# audio.net
KiCad netlist of a schematic drawn in Altium Designer
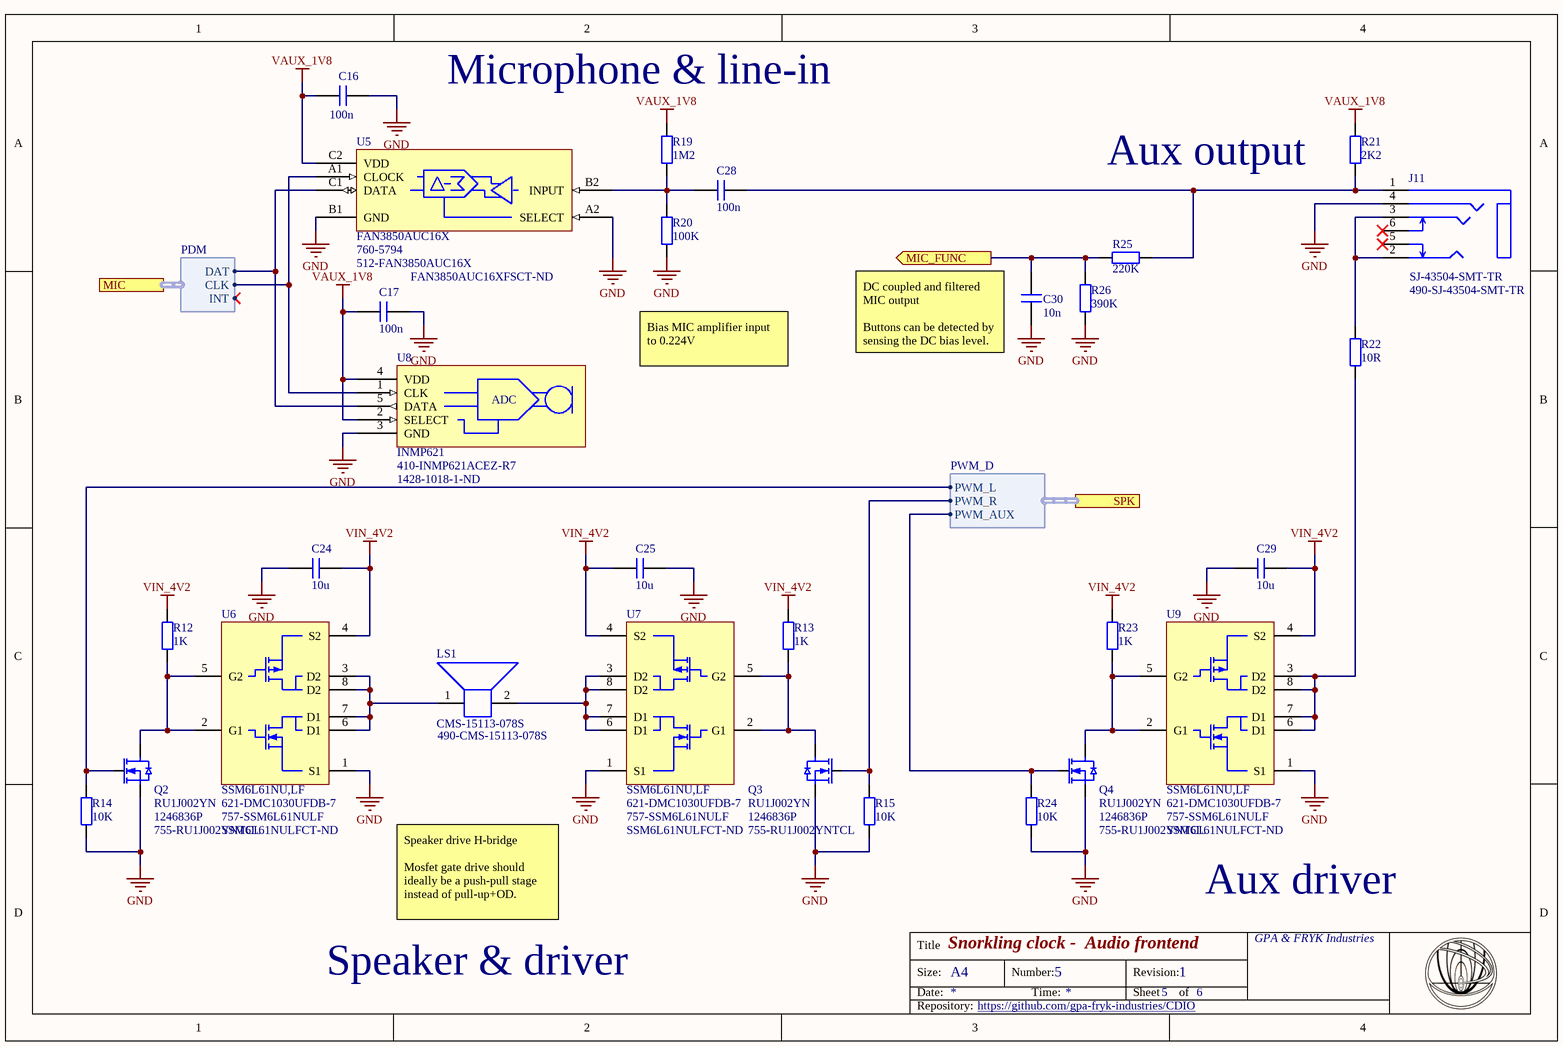
[diagram p0: audio.SchDoc]

(export (version "E")
  (design (tool "Eeschema 10.0.6"))
  (components
    (comp (ref "C16")
      (value "100n")
      (footprint "CAPC1005X06N")
      (description "Capacitor")
      (fields (field (name "Comment") "cap"))
      (libsource (lib "lib_passives") (part "cap"))
    )
    (comp (ref "C17")
      (value "100n")
      (footprint "CAPC1005X06N")
      (description "Capacitor")
      (fields (field (name "Comment") "cap"))
      (libsource (lib "lib_passives") (part "cap"))
    )
    (comp (ref "C24")
      (value "10u")
      (footprint "CAPC3216X14N")
      (description "Capacitor")
      (fields (field (name "Comment") "cap"))
      (libsource (lib "lib_passives") (part "cap"))
    )
    (comp (ref "C25")
      (value "10u")
      (footprint "CAPC3216X14N")
      (description "Capacitor")
      (fields (field (name "Comment") "cap"))
      (libsource (lib "lib_passives") (part "cap"))
    )
    (comp (ref "C28")
      (value "100n")
      (footprint "CAPC1005X06N")
      (description "Capacitor")
      (fields (field (name "Comment") "cap"))
      (libsource (lib "lib_passives") (part "cap"))
    )
    (comp (ref "C29")
      (value "10u")
      (footprint "CAPC3216X14N")
      (description "Capacitor")
      (fields (field (name "Comment") "cap"))
      (libsource (lib "lib_passives") (part "cap"))
    )
    (comp (ref "C30")
      (value "10n")
      (footprint "CAPC1005X06N")
      (description "Capacitor")
      (fields (field (name "Comment") "cap"))
      (libsource (lib "lib_passives") (part "cap"))
    )
    (comp (ref "J11")
      (value "SJ-43504-SMT-TR")
      (footprint "SJ-43504-SMT-TR")
      (description "MID MOUNT AUDIO JACK")
      (fields (field (name "SUPPLIER PART NUMBER 1") "490-SJ-43504-SMT-TR"))
      (libsource (lib "lib_cui") (part "sj-43504-smt-tr"))
    )
    (comp (ref "LS1")
      (value "CMS-15113-078S")
      (footprint "cms-15113-078s")
      (description "Speakers & Transducers 0.7W 8ohm 700Hz 15x11mm SpringContct")
      (fields (field (name "SUPPLIER PART NUMBER 1") "490-CMS-15113-078S"))
      (libsource (lib "lib_cui") (part "cms-15113-078s"))
    )
    (comp (ref "Q2")
      (value "RU1J002YN")
      (footprint "SOTFL65P210X105-3N")
      (description "N-channel 50V 200mA Small signal MOSFET")
      (fields
        (field (name "SUPPLIER PART NUMBER 1") "1246836P")
        (field (name "SUPPLIER PART NUMBER 2") "755-RU1J002YNTCL")
      )
      (libsource (lib "lib_rohm") (part "ru1j002yn"))
    )
    (comp (ref "Q3")
      (value "RU1J002YN")
      (footprint "SOTFL65P210X105-3N")
      (description "N-channel 50V 200mA Small signal MOSFET")
      (fields
        (field (name "SUPPLIER PART NUMBER 1") "1246836P")
        (field (name "SUPPLIER PART NUMBER 2") "755-RU1J002YNTCL")
      )
      (libsource (lib "lib_rohm") (part "ru1j002yn"))
    )
    (comp (ref "Q4")
      (value "RU1J002YN")
      (footprint "SOTFL65P210X105-3N")
      (description "N-channel 50V 200mA Small signal MOSFET")
      (fields
        (field (name "SUPPLIER PART NUMBER 1") "1246836P")
        (field (name "SUPPLIER PART NUMBER 2") "755-RU1J002YNTCL")
      )
      (libsource (lib "lib_rohm") (part "ru1j002yn"))
    )
    (comp (ref "R12")
      (value "1K")
      (footprint "RESC1005X04N")
      (description "Resistor")
      (fields (field (name "Comment") "res"))
      (libsource (lib "lib_passives") (part "res"))
    )
    (comp (ref "R13")
      (value "1K")
      (footprint "RESC1005X04N")
      (description "Resistor")
      (fields (field (name "Comment") "res"))
      (libsource (lib "") (part "res_1"))
    )
    (comp (ref "R14")
      (value "10K")
      (footprint "RESC1005X04N")
      (description "Resistor")
      (fields (field (name "Comment") "res"))
      (libsource (lib "lib_passives") (part "res"))
    )
    (comp (ref "R15")
      (value "10K")
      (footprint "RESC1005X04N")
      (description "Resistor")
      (fields (field (name "Comment") "res"))
      (libsource (lib "") (part "res_1"))
    )
    (comp (ref "R19")
      (value "1M2")
      (footprint "RESC1005X04N")
      (description "Resistor")
      (fields (field (name "Comment") "res"))
      (libsource (lib "lib_passives") (part "res"))
    )
    (comp (ref "R20")
      (value "100K")
      (footprint "RESC1005X04N")
      (description "Resistor")
      (fields (field (name "Comment") "res"))
      (libsource (lib "lib_passives") (part "res"))
    )
    (comp (ref "R21")
      (value "2K2")
      (footprint "RESC1005X04N")
      (description "Resistor")
      (fields (field (name "Comment") "res"))
      (libsource (lib "") (part "res_2"))
    )
    (comp (ref "R22")
      (value "10R")
      (footprint "RESC2012X06N")
      (description "Resistor")
      (fields (field (name "Comment") "res"))
      (libsource (lib "lib_passives") (part "res"))
    )
    (comp (ref "R23")
      (value "1K")
      (footprint "RESC1005X04N")
      (description "Resistor")
      (fields (field (name "Comment") "res"))
      (libsource (lib "lib_passives") (part "res"))
    )
    (comp (ref "R24")
      (value "10K")
      (footprint "RESC1005X04N")
      (description "Resistor")
      (fields (field (name "Comment") "res"))
      (libsource (lib "lib_passives") (part "res"))
    )
    (comp (ref "R25")
      (value "220K")
      (footprint "RESC1005X04N")
      (description "Resistor")
      (fields (field (name "Comment") "res"))
      (libsource (lib "") (part "res_2"))
    )
    (comp (ref "R26")
      (value "390K")
      (footprint "RESC1005X04N")
      (description "Resistor")
      (fields (field (name "Comment") "res"))
      (libsource (lib "") (part "res_3"))
    )
    (comp (ref "U5")
      (value "FAN3850AUC16X")
      (footprint "BGA6C48P2X3_86X126X30")
      (description "Microphone Pre-Amplifier with Digital Output")
      (fields
        (field (name "SUPPLIER PART NUMBER 1") "760-5794")
        (field (name "SUPPLIER PART NUMBER 2") "512-FAN3850AUC16X")
        (field (name "SUPPLIER PART NUMBER 3") "FAN3850AUC16XFSCT-ND")
      )
      (libsource (lib "lib_onsemi") (part "fan3850auc16x"))
    )
    (comp (ref "U6")
      (value "SSM6L61NU,LF")
      (footprint "SON65P200X80_HS-7N")
      (description "2 MOSFET in one package. 1 NMOS and one PMOS.")
      (fields
        (field (name "SUPPLIER PART NUMBER 1") "621-DMC1030UFDB-7")
        (field (name "SUPPLIER PART NUMBER 2") "757-SSM6L61NULF")
        (field (name "SUPPLIER PART NUMBER 3") "SSM6L61NULFCT-ND")
      )
      (libsource (lib "lib_toshiba") (part "ssm6l61nulf"))
    )
    (comp (ref "U7")
      (value "SSM6L61NU,LF")
      (footprint "SON65P200X80_HS-7N")
      (description "2 MOSFET in one package. 1 NMOS and one PMOS.")
      (fields
        (field (name "SUPPLIER PART NUMBER 1") "621-DMC1030UFDB-7")
        (field (name "SUPPLIER PART NUMBER 2") "757-SSM6L61NULF")
        (field (name "SUPPLIER PART NUMBER 3") "SSM6L61NULFCT-ND")
      )
      (libsource (lib "") (part "ssm6l61nulf_1"))
    )
    (comp (ref "U8")
      (value "INMP621")
      (footprint "SON70P300X90-4N")
      (description "Wide Dynamic Range Microphone with PDM Digital Output")
      (fields
        (field (name "SUPPLIER PART NUMBER 1") "410-INMP621ACEZ-R7")
        (field (name "SUPPLIER PART NUMBER 2") "1428-1018-1-ND")
      )
      (libsource (lib "lib_invensense") (part "inmp621"))
    )
    (comp (ref "U9")
      (value "SSM6L61NU,LF")
      (footprint "SON65P200X80_HS-7N")
      (description "2 MOSFET in one package. 1 NMOS and one PMOS.")
      (fields
        (field (name "SUPPLIER PART NUMBER 1") "621-DMC1030UFDB-7")
        (field (name "SUPPLIER PART NUMBER 2") "757-SSM6L61NULF")
        (field (name "SUPPLIER PART NUMBER 3") "SSM6L61NULFCT-ND")
      )
      (libsource (lib "lib_toshiba") (part "ssm6l61nulf"))
    )
  )
  (nets
    (net (code "3") (name "/MIC_FUNC") (class "Default")
      (node (ref "C30") (pin "2") (pinfunction "2_2") (pintype "passive"))
      (node (ref "R25") (pin "2") (pinfunction "2_2") (pintype "passive"))
      (node (ref "R26") (pin "1") (pinfunction "1_1") (pintype "passive"))
    )
    (net (code "6") (name "GND") (class "Default")
      (node (ref "C16") (pin "1") (pinfunction "1_1") (pintype "passive"))
      (node (ref "C17") (pin "1") (pinfunction "1_1") (pintype "passive"))
      (node (ref "C24") (pin "2") (pinfunction "2_2") (pintype "passive"))
      (node (ref "C25") (pin "1") (pinfunction "1_1") (pintype "passive"))
      (node (ref "C29") (pin "1") (pinfunction "1_1") (pintype "passive"))
      (node (ref "C30") (pin "1") (pinfunction "1_1") (pintype "passive"))
      (node (ref "J11") (pin "4") (pinfunction "4_4") (pintype "passive"))
      (node (ref "Q2") (pin "2") (pinfunction "S_2") (pintype "passive"))
      (node (ref "Q3") (pin "2") (pinfunction "S_2") (pintype "passive"))
      (node (ref "Q4") (pin "2") (pinfunction "S_2") (pintype "passive"))
      (node (ref "R14") (pin "1") (pinfunction "1_1") (pintype "passive"))
      (node (ref "R15") (pin "1") (pinfunction "1_1") (pintype "passive"))
      (node (ref "R20") (pin "1") (pinfunction "1_1") (pintype "passive"))
      (node (ref "R24") (pin "1") (pinfunction "1_1") (pintype "passive"))
      (node (ref "R26") (pin "2") (pinfunction "2_2") (pintype "passive"))
      (node (ref "U5") (pin "A2") (pinfunction "SELECT_A2") (pintype "input"))
      (node (ref "U5") (pin "B1") (pinfunction "GND_B1") (pintype "power_in"))
      (node (ref "U6") (pin "1") (pinfunction "S1_1") (pintype "passive"))
      (node (ref "U7") (pin "1") (pinfunction "S1_1") (pintype "passive"))
      (node (ref "U8") (pin "3") (pinfunction "GND_3") (pintype "power_in"))
      (node (ref "U9") (pin "1") (pinfunction "S1_1") (pintype "passive"))
    )
    (net (code "7") (name "Net-(C28-Pad2)") (class "Default")
      (node (ref "C28") (pin "2") (pinfunction "2_2") (pintype "passive"))
      (node (ref "J11") (pin "1") (pinfunction "1_1") (pintype "passive"))
      (node (ref "R21") (pin "2") (pinfunction "2_2") (pintype "passive"))
      (node (ref "R25") (pin "1") (pinfunction "1_1") (pintype "passive"))
    )
    (net (code "8") (name "Net-(J11-Pad2)") (class "Default")
      (node (ref "J11") (pin "2") (pinfunction "2_2") (pintype "passive"))
      (node (ref "J11") (pin "3") (pinfunction "3_3") (pintype "passive"))
      (node (ref "R22") (pin "2") (pinfunction "2_2") (pintype "passive"))
    )
    (net (code "9") (name "Net-(LS1-Pad1)") (class "Default")
      (node (ref "LS1") (pin "1") (pinfunction "1_1") (pintype "passive"))
      (node (ref "U6") (pin "3") (pinfunction "D2_3") (pintype "passive"))
      (node (ref "U6") (pin "6") (pinfunction "D1_6") (pintype "passive"))
      (node (ref "U6") (pin "7") (pinfunction "D1_7") (pintype "passive"))
      (node (ref "U6") (pin "8") (pinfunction "D2_8") (pintype "passive"))
    )
    (net (code "10") (name "Net-(LS1-Pad2)") (class "Default")
      (node (ref "LS1") (pin "2") (pinfunction "2_2") (pintype "passive"))
      (node (ref "U7") (pin "3") (pinfunction "D2_3") (pintype "passive"))
      (node (ref "U7") (pin "6") (pinfunction "D1_6") (pintype "passive"))
      (node (ref "U7") (pin "7") (pinfunction "D1_7") (pintype "passive"))
      (node (ref "U7") (pin "8") (pinfunction "D2_8") (pintype "passive"))
    )
    (net (code "11") (name "Net-(Q2-D)") (class "Default")
      (node (ref "Q2") (pin "3") (pinfunction "D_3") (pintype "passive"))
      (node (ref "R12") (pin "1") (pinfunction "1_1") (pintype "passive"))
      (node (ref "U6") (pin "2") (pinfunction "G1_2") (pintype "passive"))
      (node (ref "U6") (pin "5") (pinfunction "G2_5") (pintype "passive"))
    )
    (net (code "12") (name "Net-(Q2-G)") (class "Default")
      (node (ref "Q2") (pin "1") (pinfunction "G_1") (pintype "passive"))
      (node (ref "R14") (pin "2") (pinfunction "2_2") (pintype "passive"))
    )
    (net (code "13") (name "Net-(Q3-D)") (class "Default")
      (node (ref "Q3") (pin "3") (pinfunction "D_3") (pintype "passive"))
      (node (ref "R13") (pin "1") (pinfunction "1_1") (pintype "passive"))
      (node (ref "U7") (pin "2") (pinfunction "G1_2") (pintype "passive"))
      (node (ref "U7") (pin "5") (pinfunction "G2_5") (pintype "passive"))
    )
    (net (code "14") (name "Net-(Q3-G)") (class "Default")
      (node (ref "Q3") (pin "1") (pinfunction "G_1") (pintype "passive"))
      (node (ref "R15") (pin "2") (pinfunction "2_2") (pintype "passive"))
    )
    (net (code "15") (name "Net-(Q4-D)") (class "Default")
      (node (ref "Q4") (pin "3") (pinfunction "D_3") (pintype "passive"))
      (node (ref "R23") (pin "1") (pinfunction "1_1") (pintype "passive"))
      (node (ref "U9") (pin "2") (pinfunction "G1_2") (pintype "passive"))
      (node (ref "U9") (pin "5") (pinfunction "G2_5") (pintype "passive"))
    )
    (net (code "16") (name "Net-(Q4-G)") (class "Default")
      (node (ref "Q4") (pin "1") (pinfunction "G_1") (pintype "passive"))
      (node (ref "R24") (pin "2") (pinfunction "2_2") (pintype "passive"))
    )
    (net (code "17") (name "Net-(R22-Pad1)") (class "Default")
      (node (ref "R22") (pin "1") (pinfunction "1_1") (pintype "passive"))
      (node (ref "U9") (pin "3") (pinfunction "D2_3") (pintype "passive"))
      (node (ref "U9") (pin "6") (pinfunction "D1_6") (pintype "passive"))
      (node (ref "U9") (pin "7") (pinfunction "D1_7") (pintype "passive"))
      (node (ref "U9") (pin "8") (pinfunction "D2_8") (pintype "passive"))
    )
    (net (code "18") (name "Net-(U5-CLOCK)") (class "Default")
      (node (ref "U5") (pin "A1") (pinfunction "CLOCK_A1") (pintype "input"))
      (node (ref "U8") (pin "1") (pinfunction "CLK_1") (pintype "input"))
    )
    (net (code "19") (name "Net-(U5-DATA)") (class "Default")
      (node (ref "U5") (pin "C1") (pinfunction "DATA_C1") (pintype "bidirectional"))
      (node (ref "U8") (pin "5") (pinfunction "DATA_5") (pintype "output"))
    )
    (net (code "20") (name "Net-(U5-INPUT)") (class "Default")
      (node (ref "C28") (pin "1") (pinfunction "1_1") (pintype "passive"))
      (node (ref "R19") (pin "1") (pinfunction "1_1") (pintype "passive"))
      (node (ref "R20") (pin "2") (pinfunction "2_2") (pintype "passive"))
      (node (ref "U5") (pin "B2") (pinfunction "INPUT_B2") (pintype "input"))
    )
    (net (code "21") (name "VAUX_1V8") (class "Default")
      (node (ref "C16") (pin "2") (pinfunction "2_2") (pintype "passive"))
      (node (ref "C17") (pin "2") (pinfunction "2_2") (pintype "passive"))
      (node (ref "R19") (pin "2") (pinfunction "2_2") (pintype "passive"))
      (node (ref "R21") (pin "1") (pinfunction "1_1") (pintype "passive"))
      (node (ref "U5") (pin "C2") (pinfunction "VDD_C2") (pintype "power_in"))
      (node (ref "U8") (pin "2") (pinfunction "SELECT_2") (pintype "input"))
      (node (ref "U8") (pin "4") (pinfunction "VDD_4") (pintype "power_in"))
    )
    (net (code "22") (name "VIN_4V2") (class "Default")
      (node (ref "C24") (pin "1") (pinfunction "1_1") (pintype "passive"))
      (node (ref "C25") (pin "2") (pinfunction "2_2") (pintype "passive"))
      (node (ref "C29") (pin "2") (pinfunction "2_2") (pintype "passive"))
      (node (ref "R12") (pin "2") (pinfunction "2_2") (pintype "passive"))
      (node (ref "R13") (pin "2") (pinfunction "2_2") (pintype "passive"))
      (node (ref "R23") (pin "2") (pinfunction "2_2") (pintype "passive"))
      (node (ref "U6") (pin "4") (pinfunction "S2_4") (pintype "passive"))
      (node (ref "U7") (pin "4") (pinfunction "S2_4") (pintype "passive"))
      (node (ref "U9") (pin "4") (pinfunction "S2_4") (pintype "passive"))
    )
    (net (code "23") (name "unconnected-(J11-4-Pad5)") (class "Default")
      (node (ref "J11") (pin "5") (pinfunction "4_5") (pintype "passive+no_connect"))
    )
    (net (code "24") (name "unconnected-(J11-4-Pad6)") (class "Default")
      (node (ref "J11") (pin "6") (pinfunction "4_6") (pintype "passive+no_connect"))
    )
  )
)
